# Schematic.net
KiCad netlist of a schematic drawn in Altium Designer
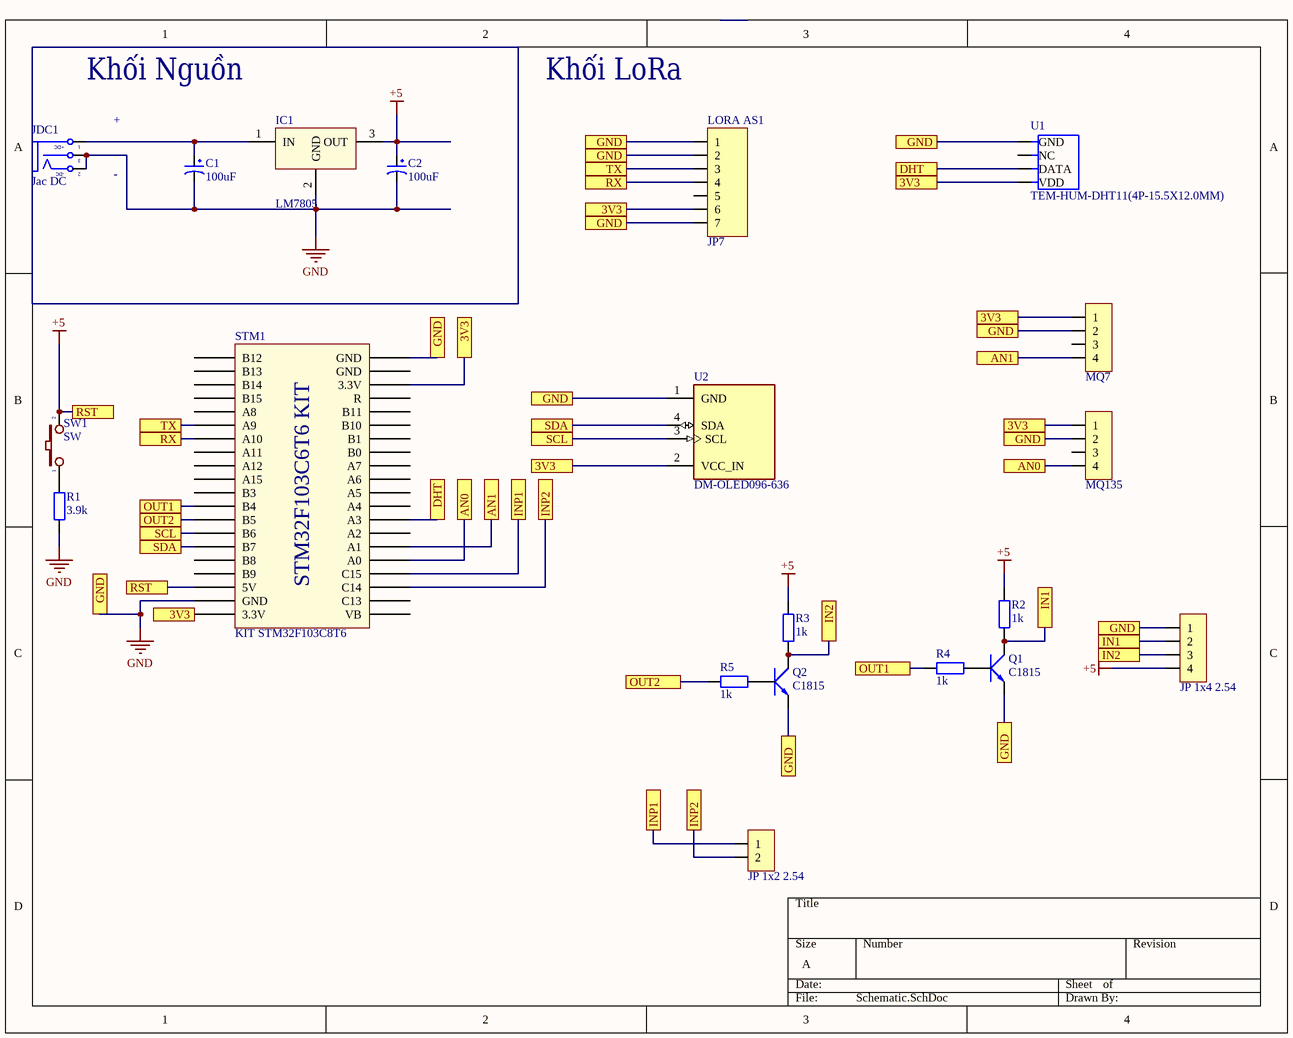
[diagram p0: Schematic.SchDoc]

(export (version "E")
  (design (tool "Eeschema 10.0.6"))
  (components
    (comp (ref "C1")
      (value "100uF")
      (footprint "Tu hoa 10mm")
      (description "Cắm")
      (libsource (lib "Capacitor") (part "Tu Hoa 100uF 100V 10x20"))
    )
    (comp (ref "C2")
      (value "100uF")
      (footprint "Tu hoa 10mm")
      (description "Cắm")
      (libsource (lib "Capacitor") (part "Tu Hoa 100uF 100V 10x20"))
    )
    (comp (ref "IC1")
      (value "LM7805")
      (footprint "QTO-220")
      (description "On ap +, from + 5 to + 24VDC")
      (libsource (lib "syhaunguyen") (part "LM78xx"))
    )
    (comp (ref "JDC1")
      (value "Jac DC")
      (footprint "DC-IN")
      (description "Jac DC input")
      (libsource (lib "syhaunguyen") (part "DCIN"))
    )
    (comp (ref "JP1")
      (value "JP 1x4 2.54")
      (footprint "JP 1x4 CC")
      (description "Cắm")
      (libsource (lib "Jump") (part "JP 1x4 2.54 Cai Cong"))
    )
    (comp (ref "JP2")
      (value "JP 1x2 2.54")
      (footprint "JP 1x2 CC")
      (description "Cắm")
      (libsource (lib "Jump") (part "JP 1x2 2.54 Cai Cong"))
    )
    (comp (ref "LORA AS1")
      (value "JP7")
      (footprint "JP7-C1C")
      (description "WR-PHD 2.54 mm Angled Socket Header")
      (fields
        (field (name "MANUFACTURER") "Würth Elektronik eiSos GmbH")
        (field (name "PARTNO") "613007143121")
        (field (name "CREATED BY") "Karrer Zheng")
      )
      (libsource (lib "LIBRARY") (part "JP7"))
    )
    (comp (ref "MQ1")
      (value "MQ7")
      (footprint "JP 1x4 CC")
      (description "Cắm")
      (libsource (lib "Jump") (part "JP 1x4 2.54 Cai Cong"))
    )
    (comp (ref "MQ2")
      (value "MQ135")
      (footprint "JP 1x4 CC")
      (description "Cắm")
      (libsource (lib "Jump") (part "JP 1x4 2.54 Cai Cong"))
    )
    (comp (ref "Q1")
      (value "C1815")
      (footprint "TO92")
      (description "NPN transistor")
      (libsource (lib "TranFet") (part "Trans C1815 DIP"))
    )
    (comp (ref "Q2")
      (value "C1815")
      (footprint "TO92")
      (description "NPN transistor")
      (libsource (lib "TranFet") (part "Trans C1815 DIP"))
    )
    (comp (ref "R1")
      (value "3.9k")
      (footprint "tro vach 1/4w")
      (description "Cắm")
      (libsource (lib "Resistor") (part "Tro Vach 1/4W 5% 9.1k"))
    )
    (comp (ref "R2")
      (value "1k")
      (footprint "tro vach 1/4w")
      (description "Cắm")
      (libsource (lib "Resistor") (part "Tro Vach 1/4W 5% 1k"))
    )
    (comp (ref "R3")
      (value "1k")
      (footprint "tro vach 1/4w")
      (description "Cắm")
      (libsource (lib "Resistor") (part "Tro Vach 1/4W 5% 1k"))
    )
    (comp (ref "R4")
      (value "1k")
      (footprint "tro vach 1/4w")
      (description "Cắm")
      (libsource (lib "Resistor") (part "Tro Vach 1/4W 5% 1k"))
    )
    (comp (ref "R5")
      (value "1k")
      (footprint "tro vach 1/4w")
      (description "Cắm")
      (libsource (lib "Resistor") (part "Tro Vach 1/4W 5% 1k"))
    )
    (comp (ref "STM1")
      (value "KIT STM32F103C8T6")
      (footprint "STM32F103 KIT")
      (description "KIT STM32F103C8T6 Bluepill")
      (libsource (lib "Module") (part "STM32f103 Bluepill"))
    )
    (comp (ref "SW1")
      (value "SW")
      (footprint "SW2")
      (description "Switch button 2 pin")
      (libsource (lib "syhaunguyen") (part "SW2"))
    )
    (comp (ref "U1")
      (value "TEM-HUM-DHT11(4P-15.5X12.0MM)")
      (footprint "SNR4-2.54-15.5X12.0X5.5MM")
      (description "Servo AC 100 ~ 120VAC Supply 10A 120V Load")
      (fields (field (name "MP") "DHT11") (field (name "MF") "Panasonic Industrial Automation Sales"))
      (libsource (lib "TEM-HUM-DHT11_4P-15.5X12.0MM_") (part "TEM-HUM-DHT11(4P-15.5X12.0MM)"))
    )
    (comp (ref "U2")
      (value "DM-OLED096-636")
      (footprint "MODULE_DM-OLED096-636")
      (description "0.96â€ 128 X 64 MONOCHROME GRAPHIC OLED DISPLAY MODULE - I2C")
      (fields (field (name "MF") "Display Module"))
      (libsource (lib "DM-OLED096-636") (part "DM-OLED096-636"))
    )
  )
  (nets
    (net (code "1") (name "+5") (class "Default")
      (node (ref "C2") (pin "1") (pinfunction "1_1") (pintype "passive"))
      (node (ref "IC1") (pin "3") (pinfunction "OUT_3") (pintype "passive"))
      (node (ref "JP1") (pin "4") (pinfunction "4_4") (pintype "passive"))
      (node (ref "R2") (pin "2") (pinfunction "2_2") (pintype "passive"))
      (node (ref "R3") (pin "2") (pinfunction "2_2") (pintype "passive"))
      (node (ref "STM1") (pin "18") (pinfunction "5V_18") (pintype "passive"))
      (node (ref "SW1") (pin "2") (pinfunction "2_2") (pintype "passive"))
    )
    (net (code "2") (name "/3V3") (class "Default")
      (node (ref "LORA AS1") (pin "6") (pinfunction "6_6") (pintype "passive"))
      (node (ref "MQ1") (pin "1") (pinfunction "1_1") (pintype "passive"))
      (node (ref "MQ2") (pin "1") (pinfunction "1_1") (pintype "passive"))
      (node (ref "STM1") (pin "20") (pinfunction "3.3V_20") (pintype "passive"))
      (node (ref "STM1") (pin "38") (pinfunction "3.3V_38") (pintype "passive"))
      (node (ref "U1") (pin "1") (pinfunction "VDD_1") (pintype "power_in"))
      (node (ref "U2") (pin "2") (pinfunction "VCC_IN_2") (pintype "power_in"))
    )
    (net (code "3") (name "/AN0") (class "Default")
      (node (ref "MQ2") (pin "4") (pinfunction "4_4") (pintype "passive"))
      (node (ref "STM1") (pin "25") (pinfunction "A0_25") (pintype "passive"))
    )
    (net (code "4") (name "/AN1") (class "Default")
      (node (ref "MQ1") (pin "4") (pinfunction "4_4") (pintype "passive"))
      (node (ref "STM1") (pin "26") (pinfunction "A1_26") (pintype "passive"))
    )
    (net (code "5") (name "/DHT") (class "Default")
      (node (ref "STM1") (pin "28") (pinfunction "A3_28") (pintype "passive"))
      (node (ref "U1") (pin "2") (pinfunction "DATA_2") (pintype "bidirectional"))
    )
    (net (code "6") (name "/IN1") (class "Default")
      (node (ref "JP1") (pin "2") (pinfunction "2_2") (pintype "passive"))
      (node (ref "Q1") (pin "2") (pinfunction "C_2") (pintype "passive"))
      (node (ref "R2") (pin "1") (pinfunction "1_1") (pintype "passive"))
    )
    (net (code "7") (name "/IN2") (class "Default")
      (node (ref "JP1") (pin "3") (pinfunction "3_3") (pintype "passive"))
      (node (ref "Q2") (pin "2") (pinfunction "C_2") (pintype "passive"))
      (node (ref "R3") (pin "1") (pinfunction "1_1") (pintype "passive"))
    )
    (net (code "8") (name "/INP1") (class "Default")
      (node (ref "JP2") (pin "1") (pinfunction "1_1") (pintype "passive"))
      (node (ref "STM1") (pin "24") (pinfunction "C15_24") (pintype "passive"))
    )
    (net (code "9") (name "/INP2") (class "Default")
      (node (ref "JP2") (pin "2") (pinfunction "2_2") (pintype "passive"))
      (node (ref "STM1") (pin "23") (pinfunction "C14_23") (pintype "passive"))
    )
    (net (code "10") (name "/OUT1") (class "Default")
      (node (ref "R4") (pin "1") (pinfunction "1_1") (pintype "passive"))
      (node (ref "STM1") (pin "12") (pinfunction "B4_12") (pintype "passive"))
    )
    (net (code "11") (name "/OUT2") (class "Default")
      (node (ref "R5") (pin "1") (pinfunction "1_1") (pintype "passive"))
      (node (ref "STM1") (pin "13") (pinfunction "B5_13") (pintype "passive"))
    )
    (net (code "12") (name "/RX") (class "Default")
      (node (ref "LORA AS1") (pin "4") (pinfunction "4_4") (pintype "passive"))
      (node (ref "STM1") (pin "7") (pinfunction "A10_7") (pintype "passive"))
    )
    (net (code "13") (name "/SCL") (class "Default")
      (node (ref "STM1") (pin "14") (pinfunction "B6_14") (pintype "passive"))
      (node (ref "U2") (pin "3") (pinfunction "SCL_3") (pintype "input"))
    )
    (net (code "14") (name "/SDA") (class "Default")
      (node (ref "STM1") (pin "15") (pinfunction "B7_15") (pintype "passive"))
      (node (ref "U2") (pin "4") (pinfunction "SDA_4") (pintype "bidirectional"))
    )
    (net (code "15") (name "/TX") (class "Default")
      (node (ref "LORA AS1") (pin "3") (pinfunction "3_3") (pintype "passive"))
      (node (ref "STM1") (pin "6") (pinfunction "A9_6") (pintype "passive"))
    )
    (net (code "16") (name "GND") (class "Default")
      (node (ref "C1") (pin "2") (pinfunction "2_2") (pintype "passive"))
      (node (ref "C2") (pin "2") (pinfunction "2_2") (pintype "passive"))
      (node (ref "IC1") (pin "2") (pinfunction "GND_2") (pintype "passive"))
      (node (ref "JDC1") (pin "2") (pinfunction "TN_2") (pintype "passive"))
      (node (ref "JDC1") (pin "3") (pinfunction "S_3") (pintype "power_in"))
      (node (ref "JP1") (pin "1") (pinfunction "1_1") (pintype "passive"))
      (node (ref "LORA AS1") (pin "1") (pinfunction "1_1") (pintype "passive"))
      (node (ref "LORA AS1") (pin "2") (pinfunction "2_2") (pintype "passive"))
      (node (ref "LORA AS1") (pin "7") (pinfunction "7_7") (pintype "passive"))
      (node (ref "MQ1") (pin "2") (pinfunction "2_2") (pintype "passive"))
      (node (ref "MQ2") (pin "2") (pinfunction "2_2") (pintype "passive"))
      (node (ref "Q1") (pin "1") (pinfunction "E_1") (pintype "passive"))
      (node (ref "Q2") (pin "1") (pinfunction "E_1") (pintype "passive"))
      (node (ref "R1") (pin "1") (pinfunction "1_1") (pintype "passive"))
      (node (ref "STM1") (pin "19") (pinfunction "GND_19") (pintype "passive"))
      (node (ref "STM1") (pin "40") (pinfunction "GND_40") (pintype "passive"))
      (node (ref "U1") (pin "4") (pinfunction "GND_4") (pintype "power_in"))
      (node (ref "U2") (pin "1") (pinfunction "GND_1") (pintype "power_in"))
    )
    (net (code "17") (name "Net-(IC1-IN)") (class "Default")
      (node (ref "C1") (pin "1") (pinfunction "1_1") (pintype "passive"))
      (node (ref "IC1") (pin "1") (pinfunction "IN_1") (pintype "passive"))
      (node (ref "JDC1") (pin "1") (pinfunction "T_1") (pintype "passive"))
    )
    (net (code "18") (name "Net-(Q1-B)") (class "Default")
      (node (ref "Q1") (pin "3") (pinfunction "B_3") (pintype "passive"))
      (node (ref "R4") (pin "2") (pinfunction "2_2") (pintype "passive"))
    )
    (net (code "19") (name "Net-(Q2-B)") (class "Default")
      (node (ref "Q2") (pin "3") (pinfunction "B_3") (pintype "passive"))
      (node (ref "R5") (pin "2") (pinfunction "2_2") (pintype "passive"))
    )
    (net (code "20") (name "Net-(R1-Pad2)") (class "Default")
      (node (ref "R1") (pin "2") (pinfunction "2_2") (pintype "passive"))
      (node (ref "SW1") (pin "1") (pinfunction "1_1") (pintype "passive"))
    )
    (net (code "21") (name "unconnected-(LORA AS1-Pad5)") (class "Default")
      (node (ref "LORA AS1") (pin "5") (pinfunction "5_5") (pintype "passive"))
    )
    (net (code "22") (name "unconnected-(MQ1-Pad3)") (class "Default")
      (node (ref "MQ1") (pin "3") (pinfunction "3_3") (pintype "passive"))
    )
    (net (code "23") (name "unconnected-(MQ2-Pad3)") (class "Default")
      (node (ref "MQ2") (pin "3") (pinfunction "3_3") (pintype "passive"))
    )
    (net (code "24") (name "unconnected-(STM1-A2-Pad27)") (class "Default")
      (node (ref "STM1") (pin "27") (pinfunction "A2_27") (pintype "passive"))
    )
    (net (code "25") (name "unconnected-(STM1-A4-Pad29)") (class "Default")
      (node (ref "STM1") (pin "29") (pinfunction "A4_29") (pintype "passive"))
    )
    (net (code "26") (name "unconnected-(STM1-A5-Pad30)") (class "Default")
      (node (ref "STM1") (pin "30") (pinfunction "A5_30") (pintype "passive"))
    )
    (net (code "27") (name "unconnected-(STM1-A6-Pad31)") (class "Default")
      (node (ref "STM1") (pin "31") (pinfunction "A6_31") (pintype "passive"))
    )
    (net (code "28") (name "unconnected-(STM1-A7-Pad32)") (class "Default")
      (node (ref "STM1") (pin "32") (pinfunction "A7_32") (pintype "passive"))
    )
    (net (code "29") (name "unconnected-(STM1-A8-Pad5)") (class "Default")
      (node (ref "STM1") (pin "5") (pinfunction "A8_5") (pintype "passive"))
    )
    (net (code "30") (name "unconnected-(STM1-A11-Pad8)") (class "Default")
      (node (ref "STM1") (pin "8") (pinfunction "A11_8") (pintype "passive"))
    )
    (net (code "31") (name "unconnected-(STM1-A12-Pad9)") (class "Default")
      (node (ref "STM1") (pin "9") (pinfunction "A12_9") (pintype "passive"))
    )
    (net (code "32") (name "unconnected-(STM1-A15-Pad10)") (class "Default")
      (node (ref "STM1") (pin "10") (pinfunction "A15_10") (pintype "passive"))
    )
    (net (code "33") (name "unconnected-(STM1-B0-Pad33)") (class "Default")
      (node (ref "STM1") (pin "33") (pinfunction "B0_33") (pintype "passive"))
    )
    (net (code "34") (name "unconnected-(STM1-B1-Pad34)") (class "Default")
      (node (ref "STM1") (pin "34") (pinfunction "B1_34") (pintype "passive"))
    )
    (net (code "35") (name "unconnected-(STM1-B3-Pad11)") (class "Default")
      (node (ref "STM1") (pin "11") (pinfunction "B3_11") (pintype "passive"))
    )
    (net (code "36") (name "unconnected-(STM1-B8-Pad16)") (class "Default")
      (node (ref "STM1") (pin "16") (pinfunction "B8_16") (pintype "passive"))
    )
    (net (code "37") (name "unconnected-(STM1-B9-Pad17)") (class "Default")
      (node (ref "STM1") (pin "17") (pinfunction "B9_17") (pintype "passive"))
    )
    (net (code "38") (name "unconnected-(STM1-B10-Pad35)") (class "Default")
      (node (ref "STM1") (pin "35") (pinfunction "B10_35") (pintype "passive"))
    )
    (net (code "39") (name "unconnected-(STM1-B11-Pad36)") (class "Default")
      (node (ref "STM1") (pin "36") (pinfunction "B11_36") (pintype "passive"))
    )
    (net (code "40") (name "unconnected-(STM1-B12-Pad1)") (class "Default")
      (node (ref "STM1") (pin "1") (pinfunction "B12_1") (pintype "passive"))
    )
    (net (code "41") (name "unconnected-(STM1-B13-Pad2)") (class "Default")
      (node (ref "STM1") (pin "2") (pinfunction "B13_2") (pintype "passive"))
    )
    (net (code "42") (name "unconnected-(STM1-B14-Pad3)") (class "Default")
      (node (ref "STM1") (pin "3") (pinfunction "B14_3") (pintype "passive"))
    )
    (net (code "43") (name "unconnected-(STM1-B15-Pad4)") (class "Default")
      (node (ref "STM1") (pin "4") (pinfunction "B15_4") (pintype "passive"))
    )
    (net (code "44") (name "unconnected-(STM1-C13-Pad22)") (class "Default")
      (node (ref "STM1") (pin "22") (pinfunction "C13_22") (pintype "passive"))
    )
    (net (code "45") (name "unconnected-(STM1-GND-Pad39)") (class "Default")
      (node (ref "STM1") (pin "39") (pinfunction "GND_39") (pintype "passive"))
    )
    (net (code "46") (name "unconnected-(STM1-R-Pad37)") (class "Default")
      (node (ref "STM1") (pin "37") (pinfunction "R_37") (pintype "passive"))
    )
    (net (code "47") (name "unconnected-(STM1-VB-Pad21)") (class "Default")
      (node (ref "STM1") (pin "21") (pinfunction "VB_21") (pintype "passive"))
    )
    (net (code "48") (name "unconnected-(U1-NC-Pad3)") (class "Default")
      (node (ref "U1") (pin "3") (pinfunction "NC_3") (pintype "passive"))
    )
  )
)
